# NEW_IR.net
KiCad netlist of a schematic drawn in EAGLE
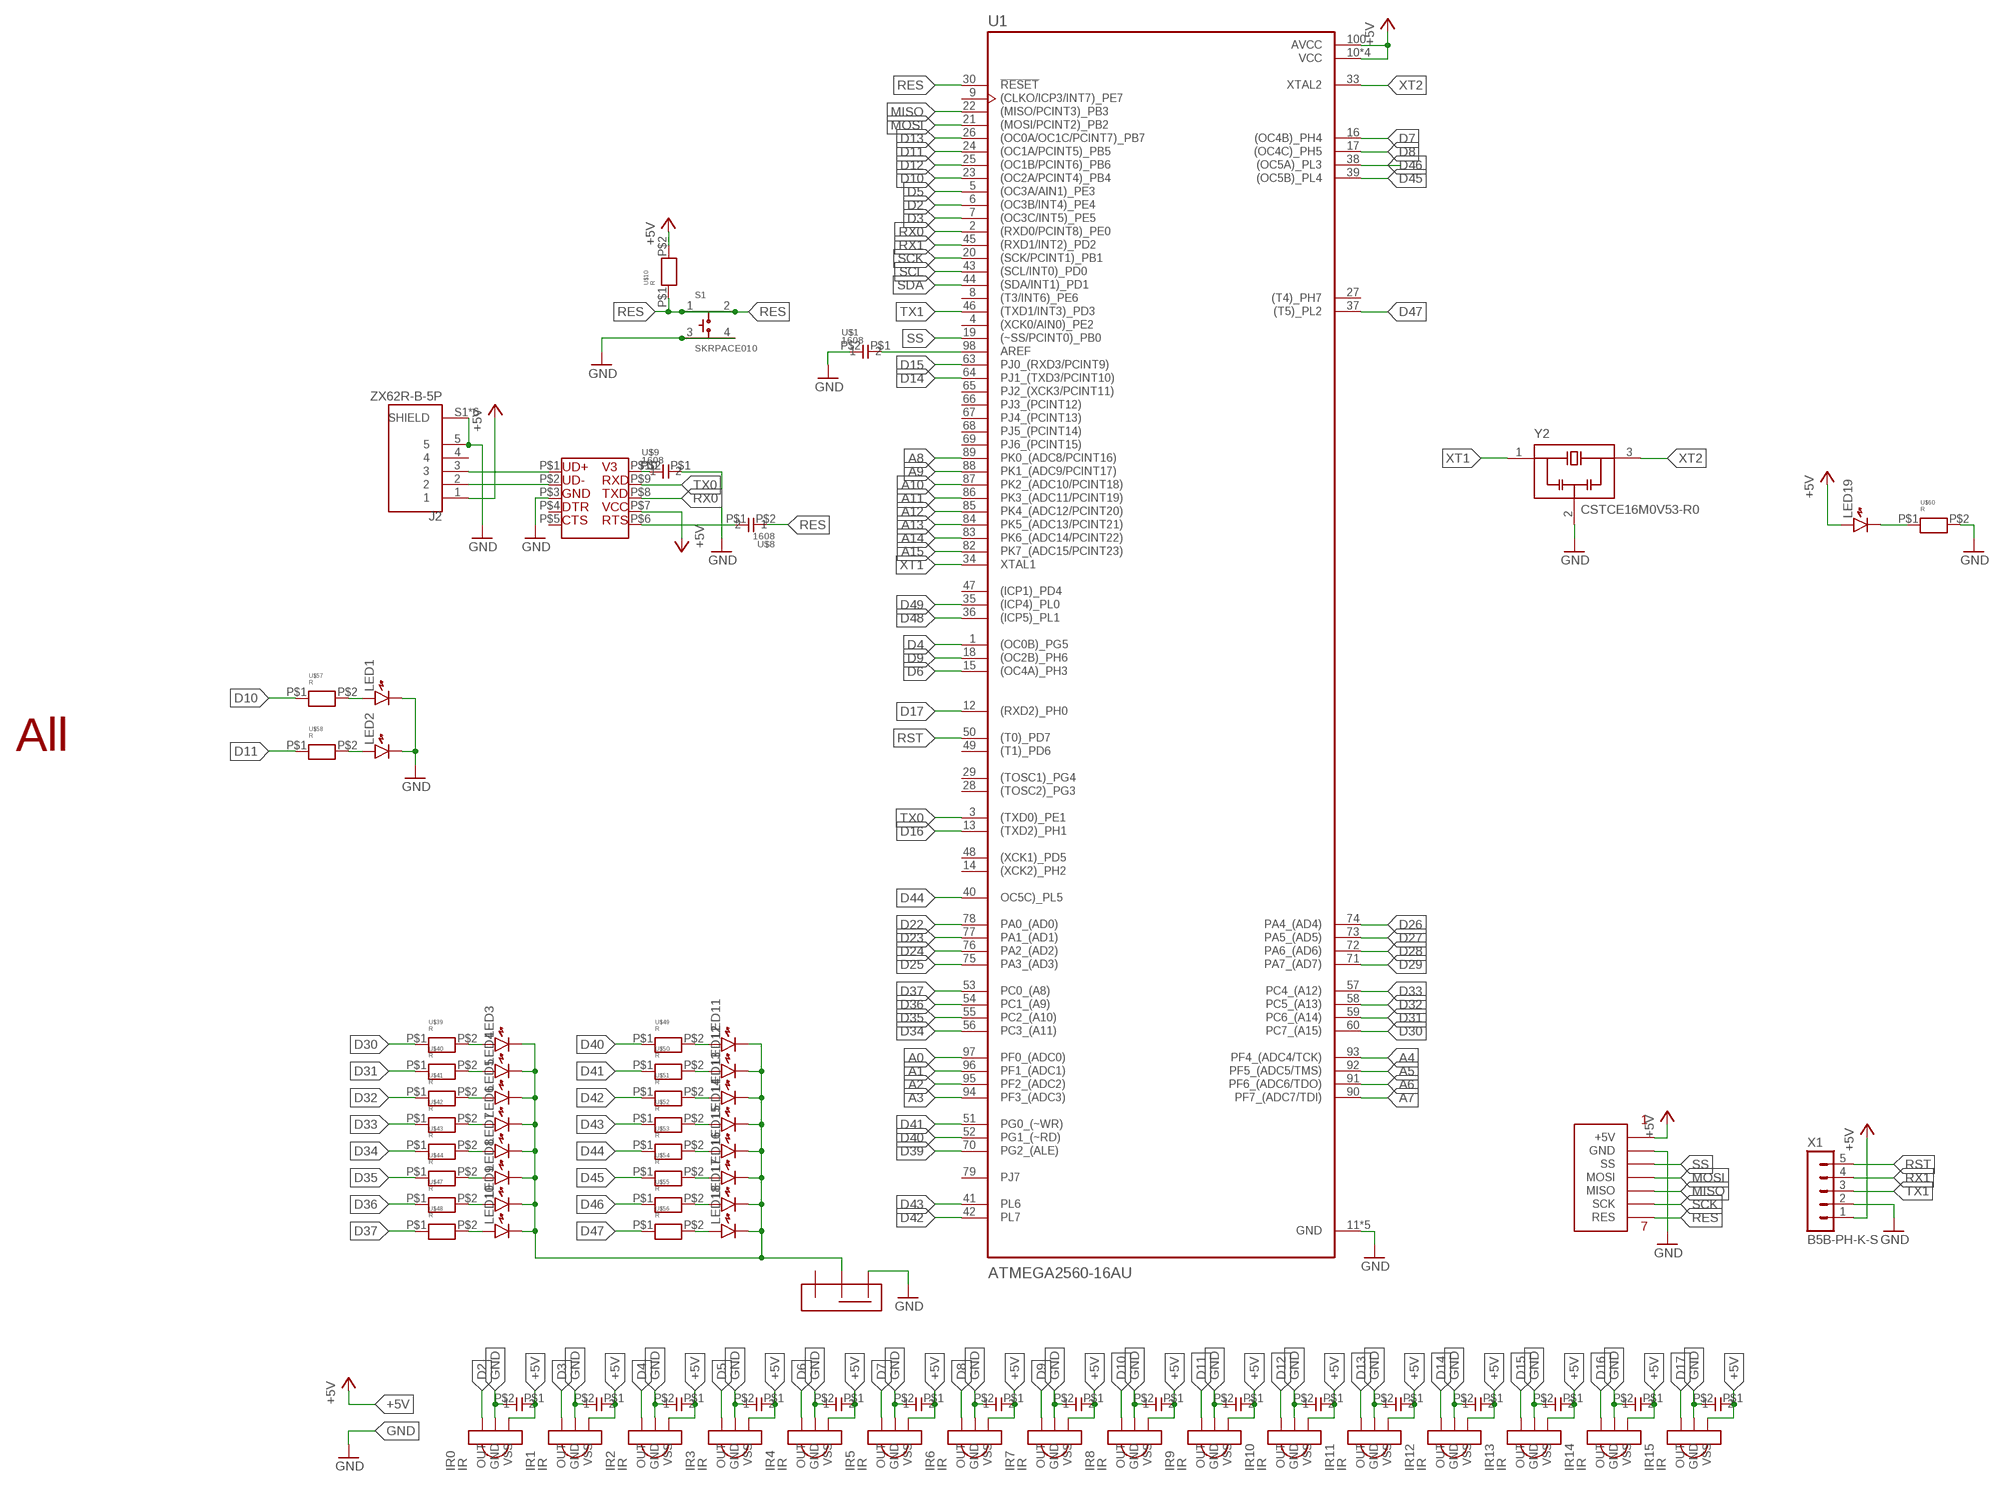
[diagram p0: schematic, sheet 1]

(export (version "E")
  (design (tool "Eeschema 10.0.6"))
  (components
    (comp (ref "IR0") (value "IR") (footprint "eagle-import:IR") (libsource (lib "eagle-import") (part "IR")))
    (comp (ref "IR1") (value "IR") (footprint "eagle-import:IR") (libsource (lib "eagle-import") (part "IR")))
    (comp (ref "IR2") (value "IR") (footprint "eagle-import:IR") (libsource (lib "eagle-import") (part "IR")))
    (comp (ref "IR3") (value "IR") (footprint "eagle-import:IR") (libsource (lib "eagle-import") (part "IR")))
    (comp (ref "IR4") (value "IR") (footprint "eagle-import:IR") (libsource (lib "eagle-import") (part "IR")))
    (comp (ref "IR5") (value "IR") (footprint "eagle-import:IR") (libsource (lib "eagle-import") (part "IR")))
    (comp (ref "IR6") (value "IR") (footprint "eagle-import:IR") (libsource (lib "eagle-import") (part "IR")))
    (comp (ref "IR7") (value "IR") (footprint "eagle-import:IR") (libsource (lib "eagle-import") (part "IR")))
    (comp (ref "IR8") (value "IR") (footprint "eagle-import:IR") (libsource (lib "eagle-import") (part "IR")))
    (comp (ref "IR9") (value "IR") (footprint "eagle-import:IR") (libsource (lib "eagle-import") (part "IR")))
    (comp (ref "IR10")
      (value "IR")
      (footprint "eagle-import:IR")
      (libsource (lib "eagle-import") (part "IR"))
    )
    (comp (ref "IR11")
      (value "IR")
      (footprint "eagle-import:IR")
      (libsource (lib "eagle-import") (part "IR"))
    )
    (comp (ref "IR12")
      (value "IR")
      (footprint "eagle-import:IR")
      (libsource (lib "eagle-import") (part "IR"))
    )
    (comp (ref "IR13")
      (value "IR")
      (footprint "eagle-import:IR")
      (libsource (lib "eagle-import") (part "IR"))
    )
    (comp (ref "IR14")
      (value "IR")
      (footprint "eagle-import:IR")
      (libsource (lib "eagle-import") (part "IR"))
    )
    (comp (ref "IR15")
      (value "IR")
      (footprint "eagle-import:IR")
      (libsource (lib "eagle-import") (part "IR"))
    )
    (comp (ref "J2")
      (value "ZX62R-B-5P")
      (footprint "eagle-import:HRS_ZX62R-B-5P")
      (fields (field (name "MF") "Hirose"))
      (libsource (lib "eagle-import") (part "ZX62R-B-5P"))
    )
    (comp (ref "LED1")
      (value "LED1608")
      (footprint "eagle-import:LED1608")
      (libsource (lib "eagle-import") (part "LED1608"))
    )
    (comp (ref "LED2")
      (value "LED1608")
      (footprint "eagle-import:LED1608")
      (libsource (lib "eagle-import") (part "LED1608"))
    )
    (comp (ref "LED3")
      (value "LED1608")
      (footprint "eagle-import:LED1608")
      (libsource (lib "eagle-import") (part "LED1608"))
    )
    (comp (ref "LED4")
      (value "LED1608")
      (footprint "eagle-import:LED1608")
      (libsource (lib "eagle-import") (part "LED1608"))
    )
    (comp (ref "LED5")
      (value "LED1608")
      (footprint "eagle-import:LED1608")
      (libsource (lib "eagle-import") (part "LED1608"))
    )
    (comp (ref "LED6")
      (value "LED1608")
      (footprint "eagle-import:LED1608")
      (libsource (lib "eagle-import") (part "LED1608"))
    )
    (comp (ref "LED7")
      (value "LED1608")
      (footprint "eagle-import:LED1608")
      (libsource (lib "eagle-import") (part "LED1608"))
    )
    (comp (ref "LED8")
      (value "LED1608")
      (footprint "eagle-import:LED1608")
      (libsource (lib "eagle-import") (part "LED1608"))
    )
    (comp (ref "LED9")
      (value "LED1608")
      (footprint "eagle-import:LED1608")
      (libsource (lib "eagle-import") (part "LED1608"))
    )
    (comp (ref "LED10")
      (value "LED1608")
      (footprint "eagle-import:LED1608")
      (libsource (lib "eagle-import") (part "LED1608"))
    )
    (comp (ref "LED11")
      (value "LED1608")
      (footprint "eagle-import:LED1608")
      (libsource (lib "eagle-import") (part "LED1608"))
    )
    (comp (ref "LED12")
      (value "LED1608")
      (footprint "eagle-import:LED1608")
      (libsource (lib "eagle-import") (part "LED1608"))
    )
    (comp (ref "LED13")
      (value "LED1608")
      (footprint "eagle-import:LED1608")
      (libsource (lib "eagle-import") (part "LED1608"))
    )
    (comp (ref "LED14")
      (value "LED1608")
      (footprint "eagle-import:LED1608")
      (libsource (lib "eagle-import") (part "LED1608"))
    )
    (comp (ref "LED15")
      (value "LED1608")
      (footprint "eagle-import:LED1608")
      (libsource (lib "eagle-import") (part "LED1608"))
    )
    (comp (ref "LED16")
      (value "LED1608")
      (footprint "eagle-import:LED1608")
      (libsource (lib "eagle-import") (part "LED1608"))
    )
    (comp (ref "LED17")
      (value "LED1608")
      (footprint "eagle-import:LED1608")
      (libsource (lib "eagle-import") (part "LED1608"))
    )
    (comp (ref "LED18")
      (value "LED1608")
      (footprint "eagle-import:LED1608")
      (libsource (lib "eagle-import") (part "LED1608"))
    )
    (comp (ref "LED19")
      (value "LED1608")
      (footprint "eagle-import:LED1608")
      (libsource (lib "eagle-import") (part "LED1608"))
    )
    (comp (ref "S1")
      (value "SKRPACE010")
      (footprint "eagle-import:SW_SKRPACE010")
      (fields (field (name "MF") "ALPS"))
      (libsource (lib "eagle-import") (part "SKRPACE010"))
    )
    (comp (ref "U$1")
      (value "1608")
      (footprint "eagle-import:CON")
      (libsource (lib "eagle-import") (part "1608"))
    )
    (comp (ref "U$2")
      (value "1608")
      (footprint "eagle-import:CON")
      (libsource (lib "eagle-import") (part "1608"))
    )
    (comp (ref "U$3")
      (value "ALL")
      (footprint "eagle-import:ALL")
      (libsource (lib "eagle-import") (part "ALL"))
    )
    (comp (ref "U$4")
      (value "1608")
      (footprint "eagle-import:CON")
      (libsource (lib "eagle-import") (part "1608"))
    )
    (comp (ref "U$5")
      (value "SSW")
      (footprint "eagle-import:SSW")
      (libsource (lib "eagle-import") (part "SSW"))
    )
    (comp (ref "U$6")
      (value "1608")
      (footprint "eagle-import:CON")
      (libsource (lib "eagle-import") (part "1608"))
    )
    (comp (ref "U$7")
      (value "CH340K")
      (footprint "eagle-import:CH340K")
      (libsource (lib "eagle-import") (part "CH340K"))
    )
    (comp (ref "U$8")
      (value "1608")
      (footprint "eagle-import:CON")
      (libsource (lib "eagle-import") (part "1608"))
    )
    (comp (ref "U$9")
      (value "1608")
      (footprint "eagle-import:CON")
      (libsource (lib "eagle-import") (part "1608"))
    )
    (comp (ref "U$10")
      (value "R")
      (footprint "eagle-import:1608")
      (libsource (lib "eagle-import") (part "R"))
    )
    (comp (ref "U$14")
      (value "1608")
      (footprint "eagle-import:CON")
      (libsource (lib "eagle-import") (part "1608"))
    )
    (comp (ref "U$16")
      (value "1608")
      (footprint "eagle-import:CON")
      (libsource (lib "eagle-import") (part "1608"))
    )
    (comp (ref "U$18")
      (value "1608")
      (footprint "eagle-import:CON")
      (libsource (lib "eagle-import") (part "1608"))
    )
    (comp (ref "U$20")
      (value "1608")
      (footprint "eagle-import:CON")
      (libsource (lib "eagle-import") (part "1608"))
    )
    (comp (ref "U$22")
      (value "1608")
      (footprint "eagle-import:CON")
      (libsource (lib "eagle-import") (part "1608"))
    )
    (comp (ref "U$24")
      (value "1608")
      (footprint "eagle-import:CON")
      (libsource (lib "eagle-import") (part "1608"))
    )
    (comp (ref "U$26")
      (value "1608")
      (footprint "eagle-import:CON")
      (libsource (lib "eagle-import") (part "1608"))
    )
    (comp (ref "U$28")
      (value "1608")
      (footprint "eagle-import:CON")
      (libsource (lib "eagle-import") (part "1608"))
    )
    (comp (ref "U$30")
      (value "1608")
      (footprint "eagle-import:CON")
      (libsource (lib "eagle-import") (part "1608"))
    )
    (comp (ref "U$32")
      (value "1608")
      (footprint "eagle-import:CON")
      (libsource (lib "eagle-import") (part "1608"))
    )
    (comp (ref "U$34")
      (value "1608")
      (footprint "eagle-import:CON")
      (libsource (lib "eagle-import") (part "1608"))
    )
    (comp (ref "U$36")
      (value "1608")
      (footprint "eagle-import:CON")
      (libsource (lib "eagle-import") (part "1608"))
    )
    (comp (ref "U$38")
      (value "1608")
      (footprint "eagle-import:CON")
      (libsource (lib "eagle-import") (part "1608"))
    )
    (comp (ref "U$39")
      (value "R")
      (footprint "eagle-import:1608")
      (libsource (lib "eagle-import") (part "R"))
    )
    (comp (ref "U$40")
      (value "R")
      (footprint "eagle-import:1608")
      (libsource (lib "eagle-import") (part "R"))
    )
    (comp (ref "U$41")
      (value "R")
      (footprint "eagle-import:1608")
      (libsource (lib "eagle-import") (part "R"))
    )
    (comp (ref "U$42")
      (value "R")
      (footprint "eagle-import:1608")
      (libsource (lib "eagle-import") (part "R"))
    )
    (comp (ref "U$43")
      (value "R")
      (footprint "eagle-import:1608")
      (libsource (lib "eagle-import") (part "R"))
    )
    (comp (ref "U$44")
      (value "R")
      (footprint "eagle-import:1608")
      (libsource (lib "eagle-import") (part "R"))
    )
    (comp (ref "U$47")
      (value "R")
      (footprint "eagle-import:1608")
      (libsource (lib "eagle-import") (part "R"))
    )
    (comp (ref "U$48")
      (value "R")
      (footprint "eagle-import:1608")
      (libsource (lib "eagle-import") (part "R"))
    )
    (comp (ref "U$49")
      (value "R")
      (footprint "eagle-import:1608")
      (libsource (lib "eagle-import") (part "R"))
    )
    (comp (ref "U$50")
      (value "R")
      (footprint "eagle-import:1608")
      (libsource (lib "eagle-import") (part "R"))
    )
    (comp (ref "U$51")
      (value "R")
      (footprint "eagle-import:1608")
      (libsource (lib "eagle-import") (part "R"))
    )
    (comp (ref "U$52")
      (value "R")
      (footprint "eagle-import:1608")
      (libsource (lib "eagle-import") (part "R"))
    )
    (comp (ref "U$53")
      (value "R")
      (footprint "eagle-import:1608")
      (libsource (lib "eagle-import") (part "R"))
    )
    (comp (ref "U$54")
      (value "R")
      (footprint "eagle-import:1608")
      (libsource (lib "eagle-import") (part "R"))
    )
    (comp (ref "U$55")
      (value "R")
      (footprint "eagle-import:1608")
      (libsource (lib "eagle-import") (part "R"))
    )
    (comp (ref "U$56")
      (value "R")
      (footprint "eagle-import:1608")
      (libsource (lib "eagle-import") (part "R"))
    )
    (comp (ref "U$57")
      (value "R")
      (footprint "eagle-import:1608")
      (libsource (lib "eagle-import") (part "R"))
    )
    (comp (ref "U$58")
      (value "R")
      (footprint "eagle-import:1608")
      (libsource (lib "eagle-import") (part "R"))
    )
    (comp (ref "U$59")
      (value "SPI")
      (footprint "eagle-import:SPI")
      (libsource (lib "eagle-import") (part "SPI"))
    )
    (comp (ref "U$60")
      (value "R")
      (footprint "eagle-import:1608")
      (libsource (lib "eagle-import") (part "R"))
    )
    (comp (ref "U1")
      (value "ATMEGA2560-16AU")
      (footprint "eagle-import:QFP50P1600X1600X120-100N")
      (fields (field (name "MF") "Microchip Technology"))
      (libsource (lib "eagle-import") (part "ATMEGA2560-16AU"))
    )
    (comp (ref "X1")
      (value "B5B-PH-K-S")
      (footprint "eagle-import:B5B-PH-K-S")
      (libsource (lib "eagle-import") (part "B5B-PH-K-S"))
    )
    (comp (ref "Y2")
      (value "CSTCE16M0V53-R0")
      (footprint "eagle-import:OSC_CSTCE16M0V53-R0")
      (fields (field (name "MANUFACTURER") "Murata"))
      (libsource (lib "eagle-import") (part "CSTCE16M0V53-R0"))
    )
  )
  (nets
    (net (code "1") (name "+5V") (class "Default")
      (node (ref "IR0") (pin "P$3") (pinfunction "VSS_P$3") (pintype "bidirectional"))
      (node (ref "IR1") (pin "P$3") (pinfunction "VSS_P$3") (pintype "bidirectional"))
      (node (ref "IR10") (pin "P$3") (pinfunction "VSS_P$3") (pintype "bidirectional"))
      (node (ref "IR11") (pin "P$3") (pinfunction "VSS_P$3") (pintype "bidirectional"))
      (node (ref "IR12") (pin "P$3") (pinfunction "VSS_P$3") (pintype "bidirectional"))
      (node (ref "IR13") (pin "P$3") (pinfunction "VSS_P$3") (pintype "bidirectional"))
      (node (ref "IR14") (pin "P$3") (pinfunction "VSS_P$3") (pintype "bidirectional"))
      (node (ref "IR15") (pin "P$3") (pinfunction "VSS_P$3") (pintype "bidirectional"))
      (node (ref "IR2") (pin "P$3") (pinfunction "VSS_P$3") (pintype "bidirectional"))
      (node (ref "IR3") (pin "P$3") (pinfunction "VSS_P$3") (pintype "bidirectional"))
      (node (ref "IR4") (pin "P$3") (pinfunction "VSS_P$3") (pintype "bidirectional"))
      (node (ref "IR5") (pin "P$3") (pinfunction "VSS_P$3") (pintype "bidirectional"))
      (node (ref "IR6") (pin "P$3") (pinfunction "VSS_P$3") (pintype "bidirectional"))
      (node (ref "IR7") (pin "P$3") (pinfunction "VSS_P$3") (pintype "bidirectional"))
      (node (ref "IR8") (pin "P$3") (pinfunction "VSS_P$3") (pintype "bidirectional"))
      (node (ref "IR9") (pin "P$3") (pinfunction "VSS_P$3") (pintype "bidirectional"))
      (node (ref "J2") (pin "1") (pinfunction "1_1") (pintype "passive"))
      (node (ref "LED19") (pin "A") (pinfunction "A_A") (pintype "passive"))
      (node (ref "U$10") (pin "P$2") (pinfunction "P$2_P$2") (pintype "bidirectional"))
      (node (ref "U$14") (pin "P$1") (pinfunction "1_P$1") (pintype "bidirectional"))
      (node (ref "U$16") (pin "P$1") (pinfunction "1_P$1") (pintype "bidirectional"))
      (node (ref "U$18") (pin "P$1") (pinfunction "1_P$1") (pintype "bidirectional"))
      (node (ref "U$2") (pin "P$1") (pinfunction "1_P$1") (pintype "bidirectional"))
      (node (ref "U$20") (pin "P$1") (pinfunction "1_P$1") (pintype "bidirectional"))
      (node (ref "U$22") (pin "P$1") (pinfunction "1_P$1") (pintype "bidirectional"))
      (node (ref "U$24") (pin "P$1") (pinfunction "1_P$1") (pintype "bidirectional"))
      (node (ref "U$26") (pin "P$1") (pinfunction "1_P$1") (pintype "bidirectional"))
      (node (ref "U$28") (pin "P$1") (pinfunction "1_P$1") (pintype "bidirectional"))
      (node (ref "U$30") (pin "P$1") (pinfunction "1_P$1") (pintype "bidirectional"))
      (node (ref "U$32") (pin "P$1") (pinfunction "1_P$1") (pintype "bidirectional"))
      (node (ref "U$34") (pin "P$1") (pinfunction "1_P$1") (pintype "bidirectional"))
      (node (ref "U$36") (pin "P$1") (pinfunction "1_P$1") (pintype "bidirectional"))
      (node (ref "U$38") (pin "P$1") (pinfunction "1_P$1") (pintype "bidirectional"))
      (node (ref "U$4") (pin "P$1") (pinfunction "1_P$1") (pintype "bidirectional"))
      (node (ref "U$59") (pin "P$1") (pinfunction "+5V_P$1") (pintype "bidirectional"))
      (node (ref "U$6") (pin "P$1") (pinfunction "1_P$1") (pintype "bidirectional"))
      (node (ref "U$7") (pin "P$7") (pinfunction "P$7_P$7") (pintype "bidirectional"))
      (node (ref "U1") (pin "10") (pinfunction "VCC_10") (pintype "power_in"))
      (node (ref "U1") (pin "100") (pinfunction "AVCC_100") (pintype "power_in"))
      (node (ref "U1") (pin "31") (pinfunction "VCC_31") (pintype "power_in"))
      (node (ref "U1") (pin "61") (pinfunction "VCC_61") (pintype "power_in"))
      (node (ref "U1") (pin "80") (pinfunction "VCC_80") (pintype "power_in"))
      (node (ref "X1") (pin "1") (pinfunction "1_1") (pintype "passive"))
    )
    (net (code "2") (name "A0") (class "Default")
      (node (ref "U1") (pin "97") (pinfunction "PF0_(ADC0)_97") (pintype "bidirectional"))
    )
    (net (code "3") (name "A1") (class "Default")
      (node (ref "U1") (pin "96") (pinfunction "PF1_(ADC1)_96") (pintype "bidirectional"))
    )
    (net (code "4") (name "A2") (class "Default")
      (node (ref "U1") (pin "95") (pinfunction "PF2_(ADC2)_95") (pintype "bidirectional"))
    )
    (net (code "5") (name "A3") (class "Default")
      (node (ref "U1") (pin "94") (pinfunction "PF3_(ADC3)_94") (pintype "bidirectional"))
    )
    (net (code "6") (name "A4") (class "Default")
      (node (ref "U1") (pin "93") (pinfunction "PF4_(ADC4/TCK)_93") (pintype "bidirectional"))
    )
    (net (code "7") (name "A5") (class "Default")
      (node (ref "U1") (pin "92") (pinfunction "PF5_(ADC5/TMS)_92") (pintype "bidirectional"))
    )
    (net (code "8") (name "A6") (class "Default")
      (node (ref "U1") (pin "91") (pinfunction "PF6_(ADC6/TDO)_91") (pintype "bidirectional"))
    )
    (net (code "9") (name "A7") (class "Default")
      (node (ref "U1") (pin "90") (pinfunction "PF7_(ADC7/TDI)_90") (pintype "bidirectional"))
    )
    (net (code "10") (name "A8") (class "Default")
      (node (ref "U1") (pin "89") (pinfunction "PK0_(ADC8/PCINT16)_89") (pintype "input"))
    )
    (net (code "11") (name "A9") (class "Default")
      (node (ref "U1") (pin "88") (pinfunction "PK1_(ADC9/PCINT17)_88") (pintype "input"))
    )
    (net (code "12") (name "A10") (class "Default")
      (node (ref "U1") (pin "87") (pinfunction "PK2_(ADC10/PCINT18)_87") (pintype "input"))
    )
    (net (code "13") (name "A11") (class "Default")
      (node (ref "U1") (pin "86") (pinfunction "PK3_(ADC11/PCINT19)_86") (pintype "input"))
    )
    (net (code "14") (name "A12") (class "Default")
      (node (ref "U1") (pin "85") (pinfunction "PK4_(ADC12/PCINT20)_85") (pintype "input"))
    )
    (net (code "15") (name "A13") (class "Default")
      (node (ref "U1") (pin "84") (pinfunction "PK5_(ADC13/PCINT21)_84") (pintype "input"))
    )
    (net (code "16") (name "A14") (class "Default")
      (node (ref "U1") (pin "83") (pinfunction "PK6_(ADC14/PCINT22)_83") (pintype "input"))
    )
    (net (code "17") (name "A15") (class "Default")
      (node (ref "U1") (pin "82") (pinfunction "PK7_(ADC15/PCINT23)_82") (pintype "input"))
    )
    (net (code "18") (name "D2") (class "Default")
      (node (ref "IR0") (pin "P$1") (pinfunction "OUT_P$1") (pintype "bidirectional"))
      (node (ref "U1") (pin "6") (pinfunction "(OC3B/INT4)_PE4_6") (pintype "input"))
    )
    (net (code "19") (name "D3") (class "Default")
      (node (ref "IR1") (pin "P$1") (pinfunction "OUT_P$1") (pintype "bidirectional"))
      (node (ref "U1") (pin "7") (pinfunction "(OC3C/INT5)_PE5_7") (pintype "input"))
    )
    (net (code "20") (name "D4") (class "Default")
      (node (ref "IR2") (pin "P$1") (pinfunction "OUT_P$1") (pintype "bidirectional"))
      (node (ref "U1") (pin "1") (pinfunction "(OC0B)_PG5_1") (pintype "bidirectional"))
    )
    (net (code "21") (name "D5") (class "Default")
      (node (ref "IR3") (pin "P$1") (pinfunction "OUT_P$1") (pintype "bidirectional"))
      (node (ref "U1") (pin "5") (pinfunction "(OC3A/AIN1)_PE3_5") (pintype "input"))
    )
    (net (code "22") (name "D6") (class "Default")
      (node (ref "IR4") (pin "P$1") (pinfunction "OUT_P$1") (pintype "bidirectional"))
      (node (ref "U1") (pin "15") (pinfunction "(OC4A)_PH3_15") (pintype "bidirectional"))
    )
    (net (code "23") (name "D7") (class "Default")
      (node (ref "IR5") (pin "P$1") (pinfunction "OUT_P$1") (pintype "bidirectional"))
      (node (ref "U1") (pin "16") (pinfunction "(OC4B)_PH4_16") (pintype "bidirectional"))
    )
    (net (code "24") (name "D8") (class "Default")
      (node (ref "IR6") (pin "P$1") (pinfunction "OUT_P$1") (pintype "bidirectional"))
      (node (ref "U1") (pin "17") (pinfunction "(OC4C)_PH5_17") (pintype "bidirectional"))
    )
    (net (code "25") (name "D9") (class "Default")
      (node (ref "IR7") (pin "P$1") (pinfunction "OUT_P$1") (pintype "bidirectional"))
      (node (ref "U1") (pin "18") (pinfunction "(OC2B)_PH6_18") (pintype "bidirectional"))
    )
    (net (code "26") (name "D10") (class "Default")
      (node (ref "IR8") (pin "P$1") (pinfunction "OUT_P$1") (pintype "bidirectional"))
      (node (ref "U$57") (pin "P$1") (pinfunction "P$1_P$1") (pintype "bidirectional"))
      (node (ref "U1") (pin "23") (pinfunction "(OC2A/PCINT4)_PB4_23") (pintype "input"))
    )
    (net (code "27") (name "D11") (class "Default")
      (node (ref "IR9") (pin "P$1") (pinfunction "OUT_P$1") (pintype "bidirectional"))
      (node (ref "U$58") (pin "P$1") (pinfunction "P$1_P$1") (pintype "bidirectional"))
      (node (ref "U1") (pin "24") (pinfunction "(OC1A/PCINT5)_PB5_24") (pintype "input"))
    )
    (net (code "28") (name "D12") (class "Default")
      (node (ref "IR10") (pin "P$1") (pinfunction "OUT_P$1") (pintype "bidirectional"))
      (node (ref "U1") (pin "25") (pinfunction "(OC1B/PCINT6)_PB6_25") (pintype "input"))
    )
    (net (code "29") (name "D13") (class "Default")
      (node (ref "IR11") (pin "P$1") (pinfunction "OUT_P$1") (pintype "bidirectional"))
      (node (ref "U1") (pin "26") (pinfunction "(OC0A/OC1C/PCINT7)_PB7_26") (pintype "input"))
    )
    (net (code "30") (name "D14") (class "Default")
      (node (ref "IR12") (pin "P$1") (pinfunction "OUT_P$1") (pintype "bidirectional"))
      (node (ref "U1") (pin "64") (pinfunction "PJ1_(TXD3/PCINT10)_64") (pintype "input"))
    )
    (net (code "31") (name "D15") (class "Default")
      (node (ref "IR13") (pin "P$1") (pinfunction "OUT_P$1") (pintype "bidirectional"))
      (node (ref "U1") (pin "63") (pinfunction "PJ0_(RXD3/PCINT9)_63") (pintype "input"))
    )
    (net (code "32") (name "D16") (class "Default")
      (node (ref "IR14") (pin "P$1") (pinfunction "OUT_P$1") (pintype "bidirectional"))
      (node (ref "U1") (pin "13") (pinfunction "(TXD2)_PH1_13") (pintype "bidirectional"))
    )
    (net (code "33") (name "D17") (class "Default")
      (node (ref "IR15") (pin "P$1") (pinfunction "OUT_P$1") (pintype "bidirectional"))
      (node (ref "U1") (pin "12") (pinfunction "(RXD2)_PH0_12") (pintype "bidirectional"))
    )
    (net (code "34") (name "D22") (class "Default")
      (node (ref "U1") (pin "78") (pinfunction "PA0_(AD0)_78") (pintype "bidirectional"))
    )
    (net (code "35") (name "D23") (class "Default")
      (node (ref "U1") (pin "77") (pinfunction "PA1_(AD1)_77") (pintype "bidirectional"))
    )
    (net (code "36") (name "D24") (class "Default")
      (node (ref "U1") (pin "76") (pinfunction "PA2_(AD2)_76") (pintype "bidirectional"))
    )
    (net (code "37") (name "D25") (class "Default")
      (node (ref "U1") (pin "75") (pinfunction "PA3_(AD3)_75") (pintype "bidirectional"))
    )
    (net (code "38") (name "D26") (class "Default")
      (node (ref "U1") (pin "74") (pinfunction "PA4_(AD4)_74") (pintype "bidirectional"))
    )
    (net (code "39") (name "D27") (class "Default")
      (node (ref "U1") (pin "73") (pinfunction "PA5_(AD5)_73") (pintype "bidirectional"))
    )
    (net (code "40") (name "D28") (class "Default")
      (node (ref "U1") (pin "72") (pinfunction "PA6_(AD6)_72") (pintype "bidirectional"))
    )
    (net (code "41") (name "D29") (class "Default")
      (node (ref "U1") (pin "71") (pinfunction "PA7_(AD7)_71") (pintype "bidirectional"))
    )
    (net (code "42") (name "D30") (class "Default")
      (node (ref "U$39") (pin "P$1") (pinfunction "P$1_P$1") (pintype "bidirectional"))
      (node (ref "U1") (pin "60") (pinfunction "PC7_(A15)_60") (pintype "bidirectional"))
    )
    (net (code "43") (name "D31") (class "Default")
      (node (ref "U$40") (pin "P$1") (pinfunction "P$1_P$1") (pintype "bidirectional"))
      (node (ref "U1") (pin "59") (pinfunction "PC6_(A14)_59") (pintype "bidirectional"))
    )
    (net (code "44") (name "D32") (class "Default")
      (node (ref "U$41") (pin "P$1") (pinfunction "P$1_P$1") (pintype "bidirectional"))
      (node (ref "U1") (pin "58") (pinfunction "PC5_(A13)_58") (pintype "bidirectional"))
    )
    (net (code "45") (name "D33") (class "Default")
      (node (ref "U$42") (pin "P$1") (pinfunction "P$1_P$1") (pintype "bidirectional"))
      (node (ref "U1") (pin "57") (pinfunction "PC4_(A12)_57") (pintype "bidirectional"))
    )
    (net (code "46") (name "D34") (class "Default")
      (node (ref "U$43") (pin "P$1") (pinfunction "P$1_P$1") (pintype "bidirectional"))
      (node (ref "U1") (pin "56") (pinfunction "PC3_(A11)_56") (pintype "bidirectional"))
    )
    (net (code "47") (name "D35") (class "Default")
      (node (ref "U$44") (pin "P$1") (pinfunction "P$1_P$1") (pintype "bidirectional"))
      (node (ref "U1") (pin "55") (pinfunction "PC2_(A10)_55") (pintype "bidirectional"))
    )
    (net (code "48") (name "D36") (class "Default")
      (node (ref "U$47") (pin "P$1") (pinfunction "P$1_P$1") (pintype "bidirectional"))
      (node (ref "U1") (pin "54") (pinfunction "PC1_(A9)_54") (pintype "bidirectional"))
    )
    (net (code "49") (name "D37") (class "Default")
      (node (ref "U$48") (pin "P$1") (pinfunction "P$1_P$1") (pintype "bidirectional"))
      (node (ref "U1") (pin "53") (pinfunction "PC0_(A8)_53") (pintype "bidirectional"))
    )
    (net (code "50") (name "D39") (class "Default")
      (node (ref "U1") (pin "70") (pinfunction "PG2_(ALE)_70") (pintype "bidirectional"))
    )
    (net (code "51") (name "D40") (class "Default")
      (node (ref "U$49") (pin "P$1") (pinfunction "P$1_P$1") (pintype "bidirectional"))
      (node (ref "U1") (pin "52") (pinfunction "PG1_(~{RD})_52") (pintype "bidirectional"))
    )
    (net (code "52") (name "D41") (class "Default")
      (node (ref "U$50") (pin "P$1") (pinfunction "P$1_P$1") (pintype "bidirectional"))
      (node (ref "U1") (pin "51") (pinfunction "PG0_(~{WR})_51") (pintype "bidirectional"))
    )
    (net (code "53") (name "D42") (class "Default")
      (node (ref "U$51") (pin "P$1") (pinfunction "P$1_P$1") (pintype "bidirectional"))
      (node (ref "U1") (pin "42") (pinfunction "PL7_42") (pintype "bidirectional"))
    )
    (net (code "54") (name "D43") (class "Default")
      (node (ref "U$52") (pin "P$1") (pinfunction "P$1_P$1") (pintype "bidirectional"))
      (node (ref "U1") (pin "41") (pinfunction "PL6_41") (pintype "bidirectional"))
    )
    (net (code "55") (name "D44") (class "Default")
      (node (ref "U$53") (pin "P$1") (pinfunction "P$1_P$1") (pintype "bidirectional"))
      (node (ref "U1") (pin "40") (pinfunction "OC5C)_PL5_40") (pintype "bidirectional"))
    )
    (net (code "56") (name "D45") (class "Default")
      (node (ref "U$54") (pin "P$1") (pinfunction "P$1_P$1") (pintype "bidirectional"))
      (node (ref "U1") (pin "39") (pinfunction "(OC5B)_PL4_39") (pintype "bidirectional"))
    )
    (net (code "57") (name "D46") (class "Default")
      (node (ref "U$55") (pin "P$1") (pinfunction "P$1_P$1") (pintype "bidirectional"))
      (node (ref "U1") (pin "38") (pinfunction "(OC5A)_PL3_38") (pintype "bidirectional"))
    )
    (net (code "58") (name "D47") (class "Default")
      (node (ref "U$56") (pin "P$1") (pinfunction "P$1_P$1") (pintype "bidirectional"))
      (node (ref "U1") (pin "37") (pinfunction "(T5)_PL2_37") (pintype "bidirectional"))
    )
    (net (code "59") (name "D48") (class "Default")
      (node (ref "U1") (pin "36") (pinfunction "(ICP5)_PL1_36") (pintype "bidirectional"))
    )
    (net (code "60") (name "D49") (class "Default")
      (node (ref "U1") (pin "35") (pinfunction "(ICP4)_PL0_35") (pintype "bidirectional"))
    )
    (net (code "61") (name "GND") (class "Default")
      (node (ref "IR0") (pin "P$2") (pinfunction "GND_P$2") (pintype "bidirectional"))
      (node (ref "IR1") (pin "P$2") (pinfunction "GND_P$2") (pintype "bidirectional"))
      (node (ref "IR10") (pin "P$2") (pinfunction "GND_P$2") (pintype "bidirectional"))
      (node (ref "IR11") (pin "P$2") (pinfunction "GND_P$2") (pintype "bidirectional"))
      (node (ref "IR12") (pin "P$2") (pinfunction "GND_P$2") (pintype "bidirectional"))
      (node (ref "IR13") (pin "P$2") (pinfunction "GND_P$2") (pintype "bidirectional"))
      (node (ref "IR14") (pin "P$2") (pinfunction "GND_P$2") (pintype "bidirectional"))
      (node (ref "IR15") (pin "P$2") (pinfunction "GND_P$2") (pintype "bidirectional"))
      (node (ref "IR2") (pin "P$2") (pinfunction "GND_P$2") (pintype "bidirectional"))
      (node (ref "IR3") (pin "P$2") (pinfunction "GND_P$2") (pintype "bidirectional"))
      (node (ref "IR4") (pin "P$2") (pinfunction "GND_P$2") (pintype "bidirectional"))
      (node (ref "IR5") (pin "P$2") (pinfunction "GND_P$2") (pintype "bidirectional"))
      (node (ref "IR6") (pin "P$2") (pinfunction "GND_P$2") (pintype "bidirectional"))
      (node (ref "IR7") (pin "P$2") (pinfunction "GND_P$2") (pintype "bidirectional"))
      (node (ref "IR8") (pin "P$2") (pinfunction "GND_P$2") (pintype "bidirectional"))
      (node (ref "IR9") (pin "P$2") (pinfunction "GND_P$2") (pintype "bidirectional"))
      (node (ref "J2") (pin "5") (pinfunction "5_5") (pintype "passive"))
      (node (ref "J2") (pin "S1") (pinfunction "SHIELD_S1") (pintype "passive"))
      (node (ref "J2") (pin "S2") (pinfunction "SHIELD_S2") (pintype "passive"))
      (node (ref "J2") (pin "S3") (pinfunction "SHIELD_S3") (pintype "passive"))
      (node (ref "J2") (pin "S4") (pinfunction "SHIELD_S4") (pintype "passive"))
      (node (ref "J2") (pin "S5") (pinfunction "SHIELD_S5") (pintype "passive"))
      (node (ref "J2") (pin "S6") (pinfunction "SHIELD_S6") (pintype "passive"))
      (node (ref "LED1") (pin "K") (pinfunction "K_K") (pintype "passive"))
      (node (ref "LED2") (pin "K") (pinfunction "K_K") (pintype "passive"))
      (node (ref "S1") (pin "3") (pinfunction "3_3") (pintype "bidirectional"))
      (node (ref "S1") (pin "4") (pinfunction "4_4") (pintype "bidirectional"))
      (node (ref "U$1") (pin "P$2") (pinfunction "2_P$2") (pintype "bidirectional"))
      (node (ref "U$14") (pin "P$2") (pinfunction "2_P$2") (pintype "bidirectional"))
      (node (ref "U$16") (pin "P$2") (pinfunction "2_P$2") (pintype "bidirectional"))
      (node (ref "U$18") (pin "P$2") (pinfunction "2_P$2") (pintype "bidirectional"))
      (node (ref "U$2") (pin "P$2") (pinfunction "2_P$2") (pintype "bidirectional"))
      (node (ref "U$20") (pin "P$2") (pinfunction "2_P$2") (pintype "bidirectional"))
      (node (ref "U$22") (pin "P$2") (pinfunction "2_P$2") (pintype "bidirectional"))
      (node (ref "U$24") (pin "P$2") (pinfunction "2_P$2") (pintype "bidirectional"))
      (node (ref "U$26") (pin "P$2") (pinfunction "2_P$2") (pintype "bidirectional"))
      (node (ref "U$28") (pin "P$2") (pinfunction "2_P$2") (pintype "bidirectional"))
      (node (ref "U$30") (pin "P$2") (pinfunction "2_P$2") (pintype "bidirectional"))
      (node (ref "U$32") (pin "P$2") (pinfunction "2_P$2") (pintype "bidirectional"))
      (node (ref "U$34") (pin "P$2") (pinfunction "2_P$2") (pintype "bidirectional"))
      (node (ref "U$36") (pin "P$2") (pinfunction "2_P$2") (pintype "bidirectional"))
      (node (ref "U$38") (pin "P$2") (pinfunction "2_P$2") (pintype "bidirectional"))
      (node (ref "U$4") (pin "P$2") (pinfunction "2_P$2") (pintype "bidirectional"))
      (node (ref "U$5") (pin "P$1") (pinfunction "P$1_P$1") (pintype "bidirectional"))
      (node (ref "U$59") (pin "P$2") (pinfunction "GND_P$2") (pintype "bidirectional"))
      (node (ref "U$6") (pin "P$2") (pinfunction "2_P$2") (pintype "bidirectional"))
      (node (ref "U$60") (pin "P$2") (pinfunction "P$2_P$2") (pintype "bidirectional"))
      (node (ref "U$7") (pin "P$3") (pinfunction "P$3_P$3") (pintype "bidirectional"))
      (node (ref "U$9") (pin "P$1") (pinfunction "1_P$1") (pintype "bidirectional"))
      (node (ref "U1") (pin "11") (pinfunction "GND_11") (pintype "power_in"))
      (node (ref "U1") (pin "32") (pinfunction "GND_32") (pintype "power_in"))
      (node (ref "U1") (pin "62") (pinfunction "GND_62") (pintype "power_in"))
      (node (ref "U1") (pin "81") (pinfunction "GND_81") (pintype "power_in"))
      (node (ref "U1") (pin "99") (pinfunction "GND_99") (pintype "power_in"))
      (node (ref "X1") (pin "2") (pinfunction "2_2") (pintype "passive"))
      (node (ref "Y2") (pin "2") (pinfunction "GND_2") (pintype "power_in"))
    )
    (net (code "62") (name "MISO") (class "Default")
      (node (ref "U$59") (pin "P$5") (pinfunction "MISO_P$5") (pintype "bidirectional"))
      (node (ref "U1") (pin "22") (pinfunction "(MISO/PCINT3)_PB3_22") (pintype "input"))
    )
    (net (code "63") (name "MOSI") (class "Default")
      (node (ref "U$59") (pin "P$4") (pinfunction "MOSI_P$4") (pintype "bidirectional"))
      (node (ref "U1") (pin "21") (pinfunction "(MOSI/PCINT2)_PB2_21") (pintype "input"))
    )
    (net (code "64") (name "Net-(J2-Pad2)") (class "Default")
      (node (ref "J2") (pin "2") (pinfunction "2_2") (pintype "passive"))
      (node (ref "U$7") (pin "P$2") (pinfunction "P$2_P$2") (pintype "bidirectional"))
    )
    (net (code "65") (name "Net-(J2-Pad3)") (class "Default")
      (node (ref "J2") (pin "3") (pinfunction "3_3") (pintype "passive"))
      (node (ref "U$7") (pin "P$1") (pinfunction "P$1_P$1") (pintype "bidirectional"))
    )
    (net (code "66") (name "Net-(LED1-PadA)") (class "Default")
      (node (ref "LED1") (pin "A") (pinfunction "A_A") (pintype "passive"))
      (node (ref "U$57") (pin "P$2") (pinfunction "P$2_P$2") (pintype "bidirectional"))
    )
    (net (code "67") (name "Net-(LED2-PadA)") (class "Default")
      (node (ref "LED2") (pin "A") (pinfunction "A_A") (pintype "passive"))
      (node (ref "U$58") (pin "P$2") (pinfunction "P$2_P$2") (pintype "bidirectional"))
    )
    (net (code "68") (name "Net-(LED3-PadA)") (class "Default")
      (node (ref "LED3") (pin "A") (pinfunction "A_A") (pintype "passive"))
      (node (ref "U$39") (pin "P$2") (pinfunction "P$2_P$2") (pintype "bidirectional"))
    )
    (net (code "69") (name "Net-(LED4-PadA)") (class "Default")
      (node (ref "LED4") (pin "A") (pinfunction "A_A") (pintype "passive"))
      (node (ref "U$40") (pin "P$2") (pinfunction "P$2_P$2") (pintype "bidirectional"))
    )
    (net (code "70") (name "Net-(LED5-PadA)") (class "Default")
      (node (ref "LED5") (pin "A") (pinfunction "A_A") (pintype "passive"))
      (node (ref "U$41") (pin "P$2") (pinfunction "P$2_P$2") (pintype "bidirectional"))
    )
    (net (code "71") (name "Net-(LED6-PadA)") (class "Default")
      (node (ref "LED6") (pin "A") (pinfunction "A_A") (pintype "passive"))
      (node (ref "U$42") (pin "P$2") (pinfunction "P$2_P$2") (pintype "bidirectional"))
    )
    (net (code "72") (name "Net-(LED7-PadA)") (class "Default")
      (node (ref "LED7") (pin "A") (pinfunction "A_A") (pintype "passive"))
      (node (ref "U$43") (pin "P$2") (pinfunction "P$2_P$2") (pintype "bidirectional"))
    )
    (net (code "73") (name "Net-(LED8-PadA)") (class "Default")
      (node (ref "LED8") (pin "A") (pinfunction "A_A") (pintype "passive"))
      (node (ref "U$44") (pin "P$2") (pinfunction "P$2_P$2") (pintype "bidirectional"))
    )
    (net (code "74") (name "Net-(LED9-PadA)") (class "Default")
      (node (ref "LED9") (pin "A") (pinfunction "A_A") (pintype "passive"))
      (node (ref "U$47") (pin "P$2") (pinfunction "P$2_P$2") (pintype "bidirectional"))
    )
    (net (code "75") (name "Net-(LED10-PadA)") (class "Default")
      (node (ref "LED10") (pin "A") (pinfunction "A_A") (pintype "passive"))
      (node (ref "U$48") (pin "P$2") (pinfunction "P$2_P$2") (pintype "bidirectional"))
    )
    (net (code "76") (name "Net-(LED11-PadA)") (class "Default")
      (node (ref "LED11") (pin "A") (pinfunction "A_A") (pintype "passive"))
      (node (ref "U$49") (pin "P$2") (pinfunction "P$2_P$2") (pintype "bidirectional"))
    )
    (net (code "77") (name "Net-(LED12-PadA)") (class "Default")
      (node (ref "LED12") (pin "A") (pinfunction "A_A") (pintype "passive"))
      (node (ref "U$50") (pin "P$2") (pinfunction "P$2_P$2") (pintype "bidirectional"))
    )
    (net (code "78") (name "Net-(LED13-PadA)") (class "Default")
      (node (ref "LED13") (pin "A") (pinfunction "A_A") (pintype "passive"))
      (node (ref "U$51") (pin "P$2") (pinfunction "P$2_P$2") (pintype "bidirectional"))
    )
    (net (code "79") (name "Net-(LED14-PadA)") (class "Default")
      (node (ref "LED14") (pin "A") (pinfunction "A_A") (pintype "passive"))
      (node (ref "U$52") (pin "P$2") (pinfunction "P$2_P$2") (pintype "bidirectional"))
    )
    (net (code "80") (name "Net-(LED15-PadA)") (class "Default")
      (node (ref "LED15") (pin "A") (pinfunction "A_A") (pintype "passive"))
      (node (ref "U$53") (pin "P$2") (pinfunction "P$2_P$2") (pintype "bidirectional"))
    )
    (net (code "81") (name "Net-(LED16-PadA)") (class "Default")
      (node (ref "LED16") (pin "A") (pinfunction "A_A") (pintype "passive"))
      (node (ref "U$54") (pin "P$2") (pinfunction "P$2_P$2") (pintype "bidirectional"))
    )
    (net (code "82") (name "Net-(LED17-PadA)") (class "Default")
      (node (ref "LED17") (pin "A") (pinfunction "A_A") (pintype "passive"))
      (node (ref "U$55") (pin "P$2") (pinfunction "P$2_P$2") (pintype "bidirectional"))
    )
    (net (code "83") (name "Net-(LED18-PadA)") (class "Default")
      (node (ref "LED18") (pin "A") (pinfunction "A_A") (pintype "passive"))
      (node (ref "U$56") (pin "P$2") (pinfunction "P$2_P$2") (pintype "bidirectional"))
    )
    (net (code "84") (name "Net-(LED19-PadK)") (class "Default")
      (node (ref "LED19") (pin "K") (pinfunction "K_K") (pintype "passive"))
      (node (ref "U$60") (pin "P$1") (pinfunction "P$1_P$1") (pintype "bidirectional"))
    )
    (net (code "85") (name "Net-(U$1-1)") (class "Default")
      (node (ref "U$1") (pin "P$1") (pinfunction "1_P$1") (pintype "bidirectional"))
      (node (ref "U1") (pin "98") (pinfunction "AREF_98") (pintype "input"))
    )
    (net (code "86") (name "Net-(U$5-P$2)") (class "Default")
      (node (ref "LED10") (pin "K") (pinfunction "K_K") (pintype "passive"))
      (node (ref "LED11") (pin "K") (pinfunction "K_K") (pintype "passive"))
      (node (ref "LED12") (pin "K") (pinfunction "K_K") (pintype "passive"))
      (node (ref "LED13") (pin "K") (pinfunction "K_K") (pintype "passive"))
      (node (ref "LED14") (pin "K") (pinfunction "K_K") (pintype "passive"))
      (node (ref "LED15") (pin "K") (pinfunction "K_K") (pintype "passive"))
      (node (ref "LED16") (pin "K") (pinfunction "K_K") (pintype "passive"))
      (node (ref "LED17") (pin "K") (pinfunction "K_K") (pintype "passive"))
      (node (ref "LED18") (pin "K") (pinfunction "K_K") (pintype "passive"))
      (node (ref "LED3") (pin "K") (pinfunction "K_K") (pintype "passive"))
      (node (ref "LED4") (pin "K") (pinfunction "K_K") (pintype "passive"))
      (node (ref "LED5") (pin "K") (pinfunction "K_K") (pintype "passive"))
      (node (ref "LED6") (pin "K") (pinfunction "K_K") (pintype "passive"))
      (node (ref "LED7") (pin "K") (pinfunction "K_K") (pintype "passive"))
      (node (ref "LED8") (pin "K") (pinfunction "K_K") (pintype "passive"))
      (node (ref "LED9") (pin "K") (pinfunction "K_K") (pintype "passive"))
      (node (ref "U$5") (pin "P$3") (pinfunction "P$2_P$3") (pintype "bidirectional"))
    )
    (net (code "87") (name "Net-(U$8-1)") (class "Default")
      (node (ref "U$7") (pin "P$6") (pinfunction "P$6_P$6") (pintype "bidirectional"))
      (node (ref "U$8") (pin "P$1") (pinfunction "1_P$1") (pintype "bidirectional"))
    )
    (net (code "88") (name "Net-(U$9-2)") (class "Default")
      (node (ref "U$7") (pin "P$10") (pinfunction "P$10_P$10") (pintype "bidirectional"))
      (node (ref "U$9") (pin "P$2") (pinfunction "2_P$2") (pintype "bidirectional"))
    )
    (net (code "89") (name "RES") (class "Default")
      (node (ref "S1") (pin "1") (pinfunction "1_1") (pintype "bidirectional"))
      (node (ref "S1") (pin "2") (pinfunction "2_2") (pintype "bidirectional"))
      (node (ref "U$10") (pin "P$1") (pinfunction "P$1_P$1") (pintype "bidirectional"))
      (node (ref "U$59") (pin "P$7") (pinfunction "RES_P$7") (pintype "bidirectional"))
      (node (ref "U$8") (pin "P$2") (pinfunction "2_P$2") (pintype "bidirectional"))
      (node (ref "U1") (pin "30") (pinfunction "~{RESET}_30") (pintype "input"))
    )
    (net (code "90") (name "RST") (class "Default")
      (node (ref "U1") (pin "50") (pinfunction "(T0)_PD7_50") (pintype "bidirectional"))
      (node (ref "X1") (pin "5") (pinfunction "5_5") (pintype "passive"))
    )
    (net (code "91") (name "RX0") (class "Default")
      (node (ref "U$7") (pin "P$8") (pinfunction "P$8_P$8") (pintype "bidirectional"))
      (node (ref "U1") (pin "2") (pinfunction "(RXD0/PCINT8)_PE0_2") (pintype "input"))
    )
    (net (code "92") (name "RX1") (class "Default")
      (node (ref "U1") (pin "45") (pinfunction "(RXD1/INT2)_PD2_45") (pintype "input"))
      (node (ref "X1") (pin "4") (pinfunction "4_4") (pintype "passive"))
    )
    (net (code "93") (name "SCK") (class "Default")
      (node (ref "U$59") (pin "P$6") (pinfunction "SCK_P$6") (pintype "bidirectional"))
      (node (ref "U1") (pin "20") (pinfunction "(SCK/PCINT1)_PB1_20") (pintype "input"))
    )
    (net (code "94") (name "SCL") (class "Default")
      (node (ref "U1") (pin "43") (pinfunction "(SCL/INT0)_PD0_43") (pintype "input"))
    )
    (net (code "95") (name "SDA") (class "Default")
      (node (ref "U1") (pin "44") (pinfunction "(SDA/INT1)_PD1_44") (pintype "input"))
    )
    (net (code "96") (name "SS") (class "Default")
      (node (ref "U$59") (pin "P$3") (pinfunction "SS_P$3") (pintype "bidirectional"))
      (node (ref "U1") (pin "19") (pinfunction "(~{SS/PCINT0})_PB0_19") (pintype "input"))
    )
    (net (code "97") (name "TX0") (class "Default")
      (node (ref "U$7") (pin "P$9") (pinfunction "P$9_P$9") (pintype "bidirectional"))
      (node (ref "U1") (pin "3") (pinfunction "(TXD0)_PE1_3") (pintype "bidirectional"))
    )
    (net (code "98") (name "TX1") (class "Default")
      (node (ref "U1") (pin "46") (pinfunction "(TXD1/INT3)_PD3_46") (pintype "input"))
      (node (ref "X1") (pin "3") (pinfunction "3_3") (pintype "passive"))
    )
    (net (code "99") (name "XT1") (class "Default")
      (node (ref "U1") (pin "34") (pinfunction "XTAL1_34") (pintype "input"))
      (node (ref "Y2") (pin "1") (pinfunction "IN_1") (pintype "input"))
    )
    (net (code "100") (name "XT2") (class "Default")
      (node (ref "U1") (pin "33") (pinfunction "XTAL2_33") (pintype "output"))
      (node (ref "Y2") (pin "3") (pinfunction "OUT_3") (pintype "output"))
    )
    (net (code "101") (name "unconnected-(J2-Pad4)") (class "Default")
      (node (ref "J2") (pin "4") (pinfunction "4_4") (pintype "passive"))
    )
    (net (code "102") (name "unconnected-(U$5-P$3-PadP$2)") (class "Default")
      (node (ref "U$5") (pin "P$2") (pinfunction "P$3_P$2") (pintype "bidirectional"))
    )
    (net (code "103") (name "unconnected-(U$7-PadP$4)") (class "Default")
      (node (ref "U$7") (pin "P$4") (pinfunction "P$4_P$4") (pintype "bidirectional"))
    )
    (net (code "104") (name "unconnected-(U$7-PadP$5)") (class "Default")
      (node (ref "U$7") (pin "P$5") (pinfunction "P$5_P$5") (pintype "bidirectional"))
    )
    (net (code "105") (name "unconnected-(U1-(CLKO{slash}ICP3{slash}INT7)_PE7-Pad9)") (class "Default")
      (node (ref "U1") (pin "9") (pinfunction "(CLKO/ICP3/INT7)_PE7_9") (pintype "input"))
    )
    (net (code "106") (name "unconnected-(U1-(ICP1)_PD4-Pad47)") (class "Default")
      (node (ref "U1") (pin "47") (pinfunction "(ICP1)_PD4_47") (pintype "bidirectional"))
    )
    (net (code "107") (name "unconnected-(U1-(T1)_PD6-Pad49)") (class "Default")
      (node (ref "U1") (pin "49") (pinfunction "(T1)_PD6_49") (pintype "bidirectional"))
    )
    (net (code "108") (name "unconnected-(U1-(T3{slash}INT6)_PE6-Pad8)") (class "Default")
      (node (ref "U1") (pin "8") (pinfunction "(T3/INT6)_PE6_8") (pintype "input"))
    )
    (net (code "109") (name "unconnected-(U1-(T4)_PH7-Pad27)") (class "Default")
      (node (ref "U1") (pin "27") (pinfunction "(T4)_PH7_27") (pintype "bidirectional"))
    )
    (net (code "110") (name "unconnected-(U1-(TOSC1)_PG4-Pad29)") (class "Default")
      (node (ref "U1") (pin "29") (pinfunction "(TOSC1)_PG4_29") (pintype "bidirectional"))
    )
    (net (code "111") (name "unconnected-(U1-(TOSC2)_PG3-Pad28)") (class "Default")
      (node (ref "U1") (pin "28") (pinfunction "(TOSC2)_PG3_28") (pintype "bidirectional"))
    )
    (net (code "112") (name "unconnected-(U1-(XCK0{slash}AIN0)_PE2-Pad4)") (class "Default")
      (node (ref "U1") (pin "4") (pinfunction "(XCK0/AIN0)_PE2_4") (pintype "input"))
    )
    (net (code "113") (name "unconnected-(U1-(XCK1)_PD5-Pad48)") (class "Default")
      (node (ref "U1") (pin "48") (pinfunction "(XCK1)_PD5_48") (pintype "bidirectional"))
    )
    (net (code "114") (name "unconnected-(U1-(XCK2)_PH2-Pad14)") (class "Default")
      (node (ref "U1") (pin "14") (pinfunction "(XCK2)_PH2_14") (pintype "bidirectional"))
    )
    (net (code "115") (name "unconnected-(U1-PJ2_(XCK3{slash}PCINT11)-Pad65)") (class "Default")
      (node (ref "U1") (pin "65") (pinfunction "PJ2_(XCK3/PCINT11)_65") (pintype "input"))
    )
    (net (code "116") (name "unconnected-(U1-PJ3_(PCINT12)-Pad66)") (class "Default")
      (node (ref "U1") (pin "66") (pinfunction "PJ3_(PCINT12)_66") (pintype "input"))
    )
    (net (code "117") (name "unconnected-(U1-PJ4_(PCINT13)-Pad67)") (class "Default")
      (node (ref "U1") (pin "67") (pinfunction "PJ4_(PCINT13)_67") (pintype "input"))
    )
    (net (code "118") (name "unconnected-(U1-PJ5_(PCINT14)-Pad68)") (class "Default")
      (node (ref "U1") (pin "68") (pinfunction "PJ5_(PCINT14)_68") (pintype "input"))
    )
    (net (code "119") (name "unconnected-(U1-PJ6_(PCINT15)-Pad69)") (class "Default")
      (node (ref "U1") (pin "69") (pinfunction "PJ6_(PCINT15)_69") (pintype "input"))
    )
    (net (code "120") (name "unconnected-(U1-PJ7-Pad79)") (class "Default")
      (node (ref "U1") (pin "79") (pinfunction "PJ7_79") (pintype "bidirectional"))
    )
  )
)
